# ModuleCarrier-xDot.net
KiCad netlist of a schematic drawn in EAGLE
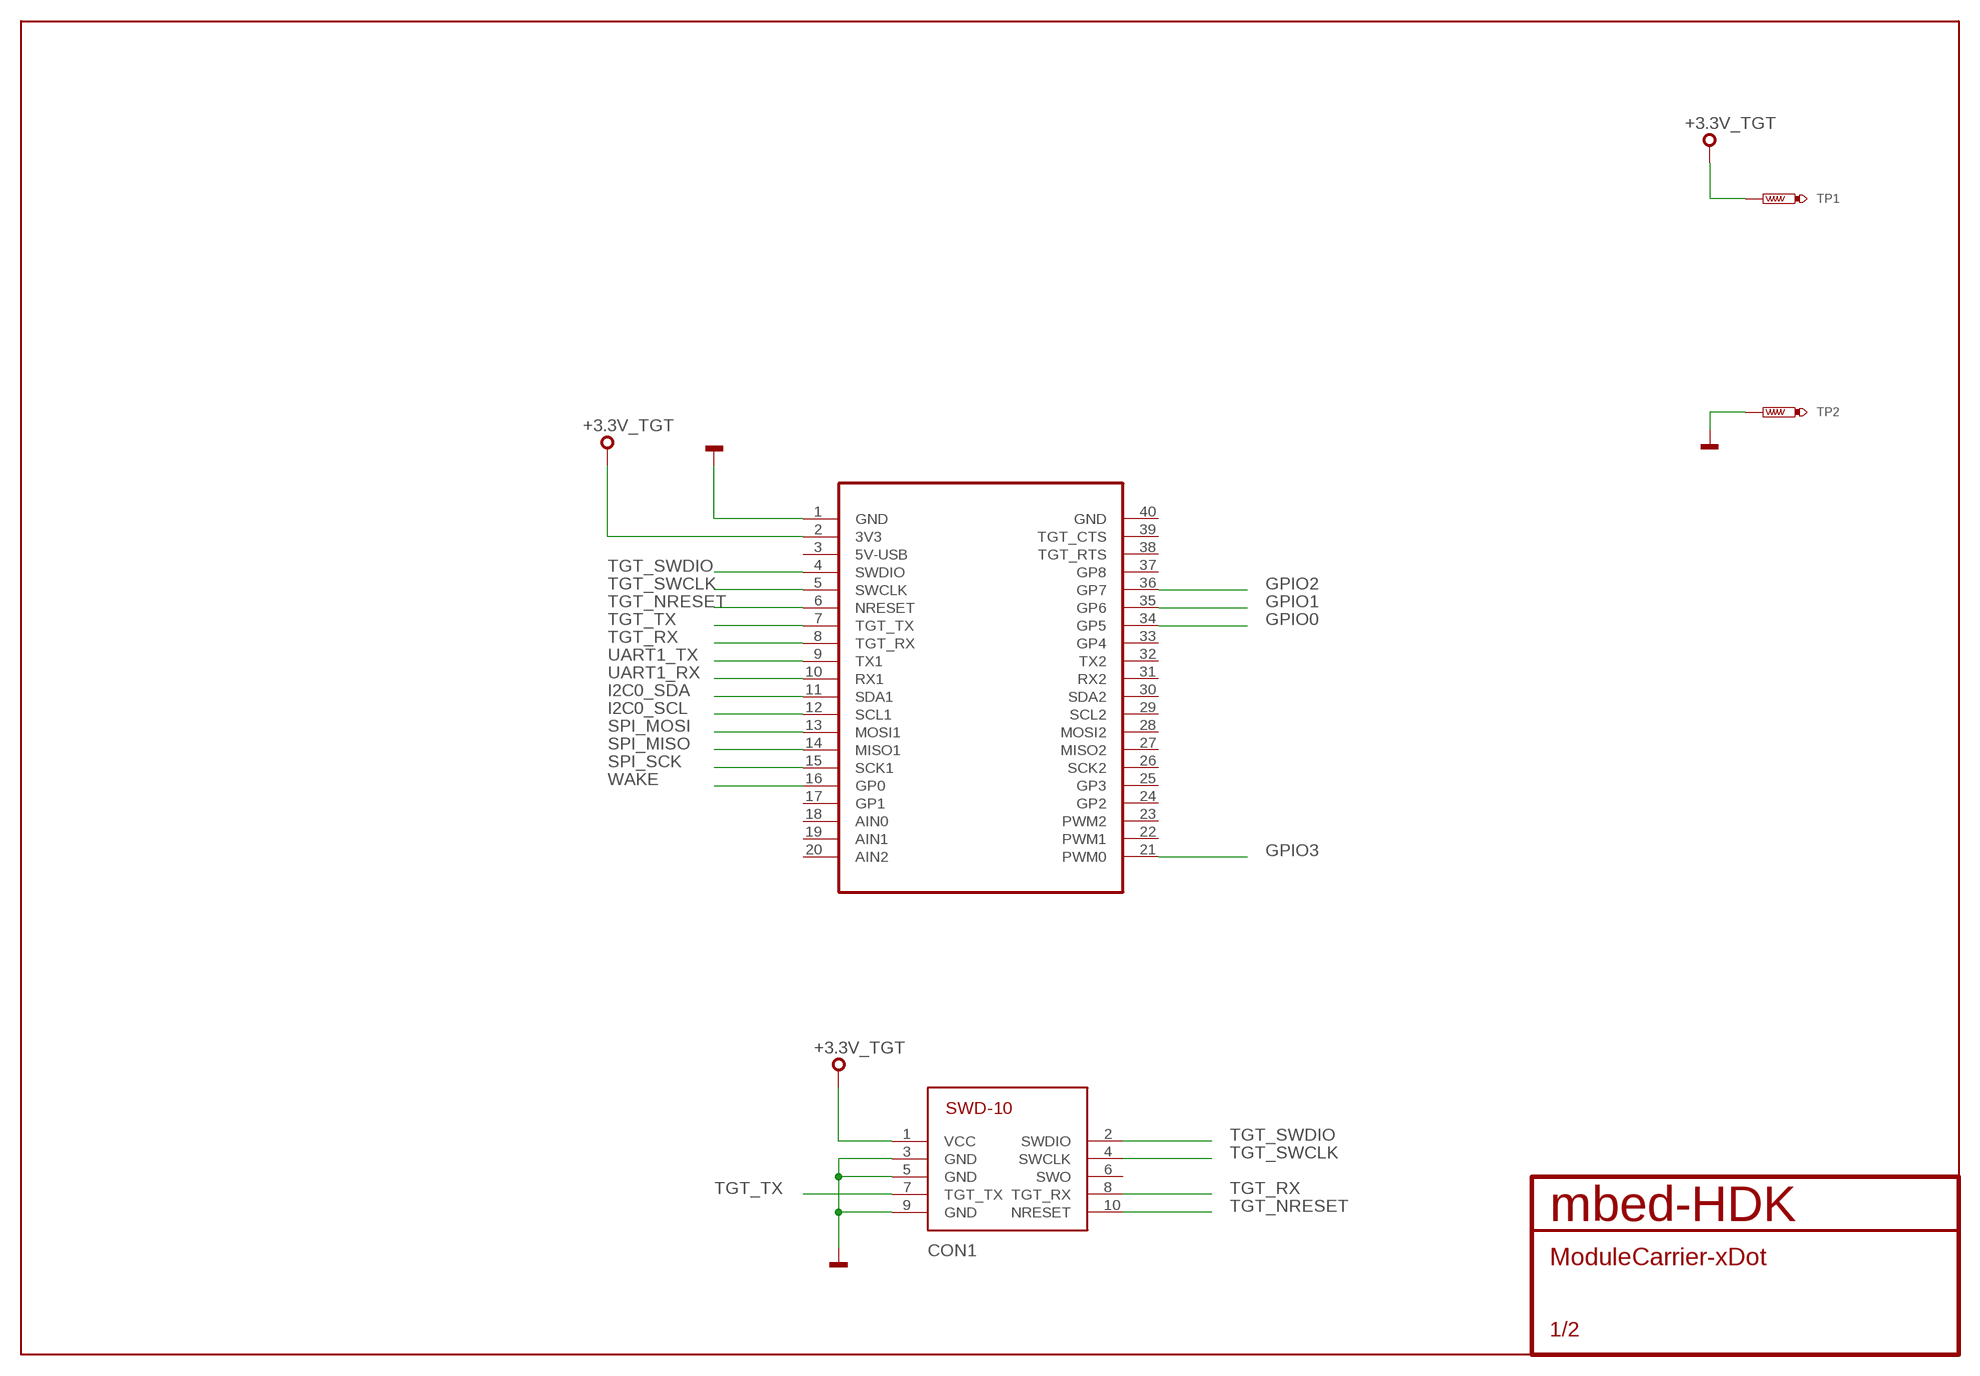
[diagram p0: schematic, sheet 1]
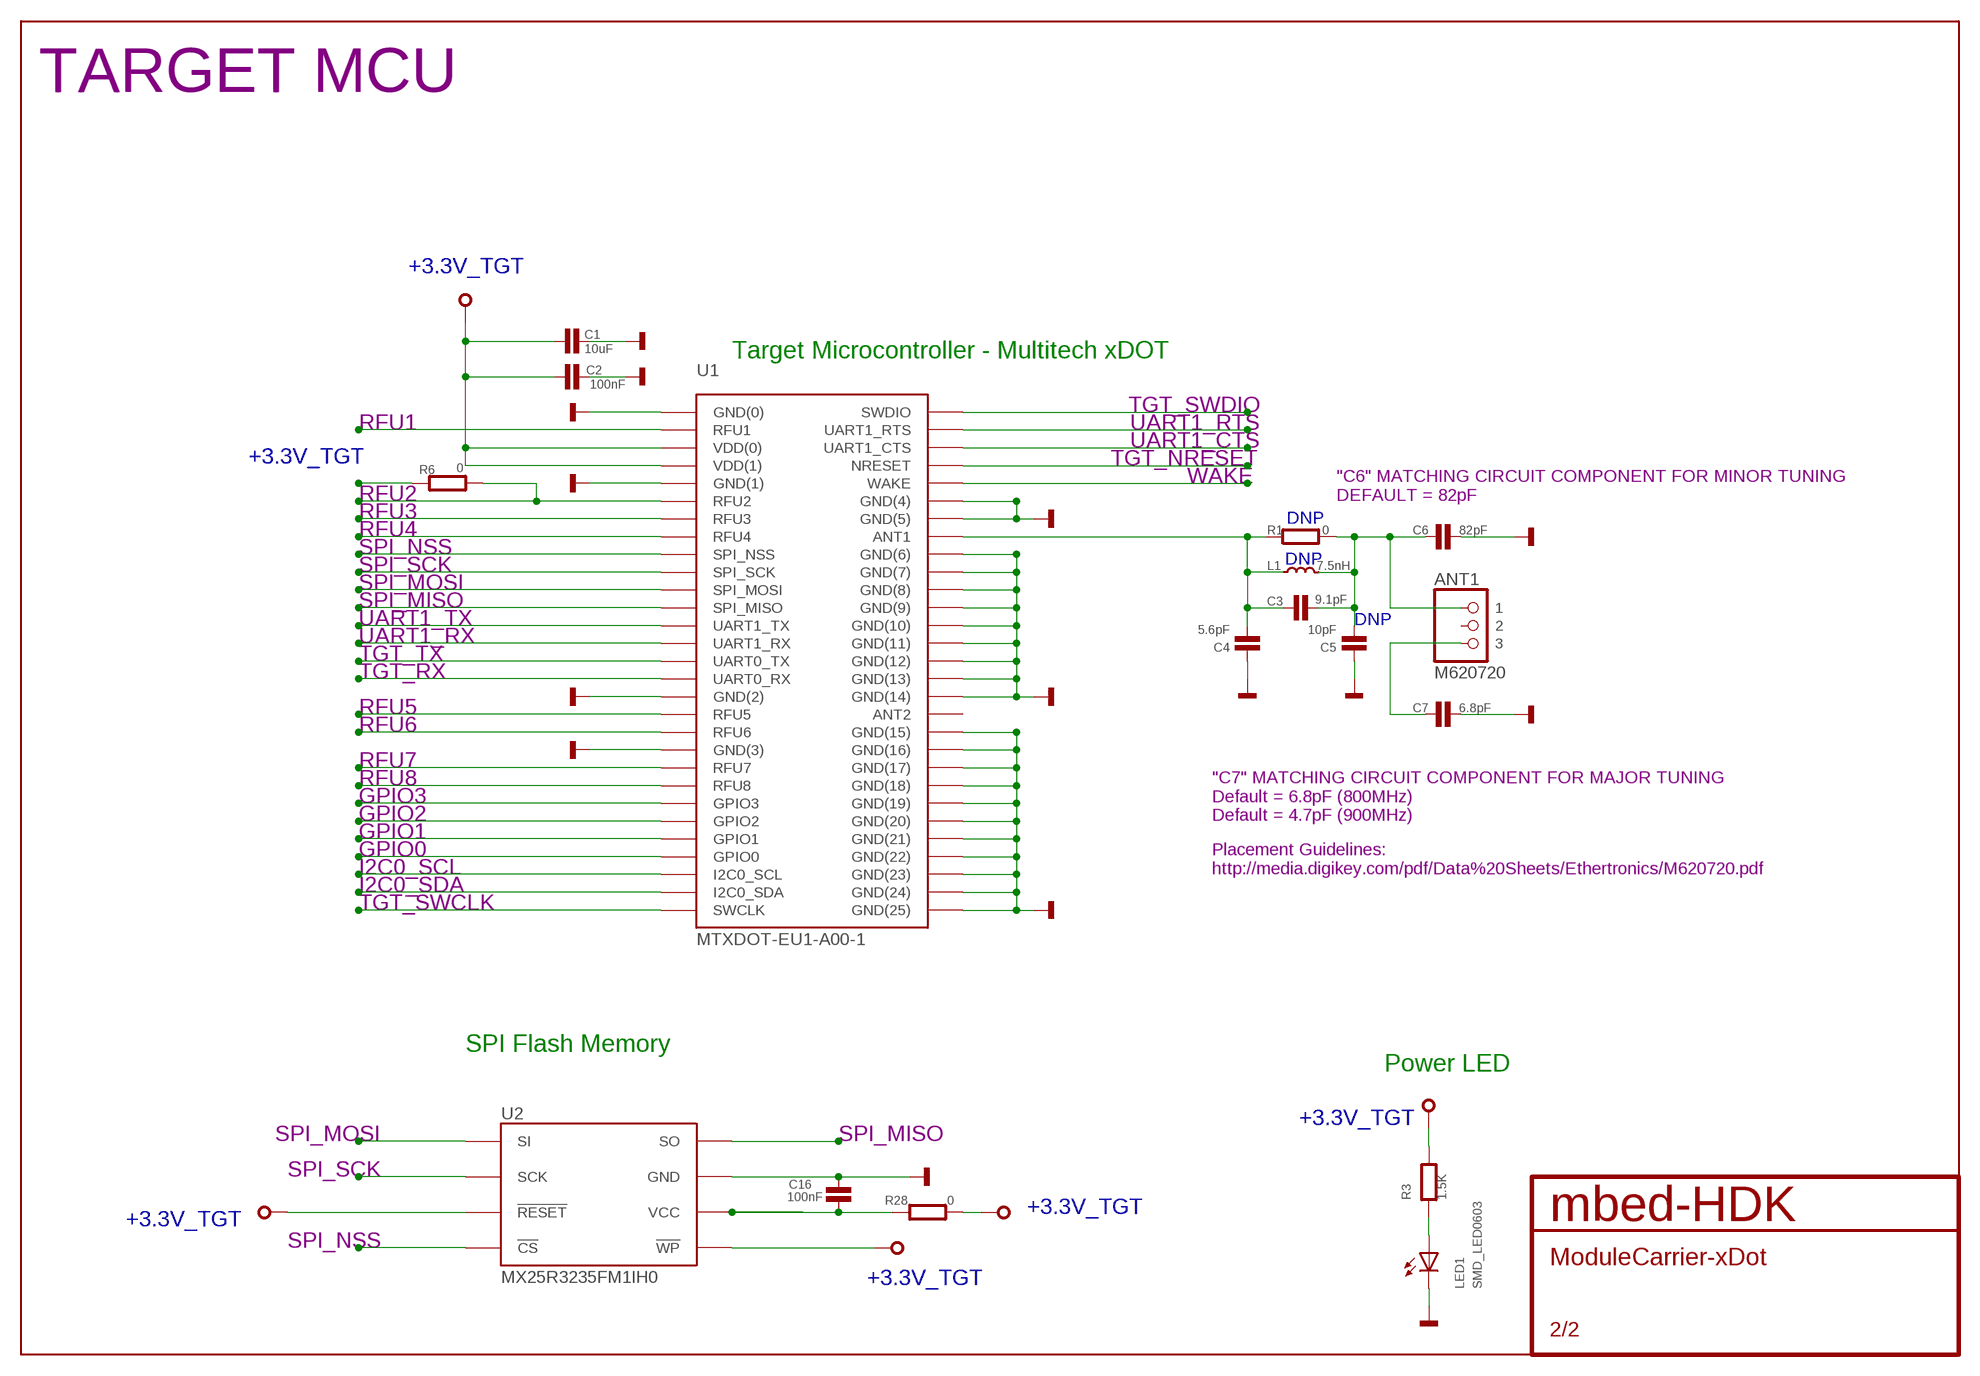
[diagram p1: schematic, sheet 2]

(export (version "E")
  (design (tool "Eeschema 10.0.6"))
  (components
    (comp (ref "CON1")
      (value "SWD-10/TC2050_SMD")
      (footprint "eagle-import:FTSH-105-02")
      (libsource (lib "eagle-import") (part "SWD-10/TC2050_SMD"))
    )
    (comp (ref "TP1")
      (value "TEST-POINT-50R-PTH")
      (footprint "eagle-import:TP50-PTH")
      (libsource (lib "eagle-import") (part "TEST-POINT-50R-PTH"))
    )
    (comp (ref "TP2")
      (value "TEST-POINT-50R-PTH")
      (footprint "eagle-import:TP50-PTH")
      (libsource (lib "eagle-import") (part "TEST-POINT-50R-PTH"))
    )
    (comp (ref "U$1")
      (value "MODULE_DAUGHTER")
      (footprint "eagle-import:MODULE_DAUGHTER")
      (libsource (lib "eagle-import") (part "MODULE_DAUGHTER"))
    )
    (comp (ref "ANT1")
      (value "M620720")
      (footprint "eagle-import:M620720")
      (fields (field (name "MF") "Ethertronics"))
      (libsource (lib "eagle-import") (part "M620720"))
    )
    (comp (ref "C1")
      (value "10uF")
      (footprint "eagle-import:0603")
      (libsource (lib "eagle-import") (part "CAPACITOR0603"))
    )
    (comp (ref "C2")
      (value "100nF")
      (footprint "eagle-import:0603")
      (libsource (lib "eagle-import") (part "CAPACITOR0603"))
    )
    (comp (ref "C3")
      (value "9.1pF")
      (footprint "eagle-import:0402")
      (libsource (lib "eagle-import") (part "CAPACITOR0402"))
    )
    (comp (ref "C4")
      (value "5.6pF")
      (footprint "eagle-import:0402")
      (libsource (lib "eagle-import") (part "CAPACITOR0402"))
    )
    (comp (ref "C5")
      (value "10pF")
      (footprint "eagle-import:0402")
      (libsource (lib "eagle-import") (part "CAPACITOR0402"))
    )
    (comp (ref "C6")
      (value "82pF")
      (footprint "eagle-import:0402")
      (libsource (lib "eagle-import") (part "CAPACITOR0402"))
    )
    (comp (ref "C7")
      (value "6.8pF")
      (footprint "eagle-import:0402")
      (libsource (lib "eagle-import") (part "CAPACITOR0402"))
    )
    (comp (ref "C16")
      (value "100nF")
      (footprint "eagle-import:0603")
      (libsource (lib "eagle-import") (part "CAPACITOR0603"))
    )
    (comp (ref "L1")
      (value "7.5nH")
      (footprint "eagle-import:0402")
      (libsource (lib "eagle-import") (part "INDUCTOR0402"))
    )
    (comp (ref "LED1")
      (value "SMD_LED0603")
      (footprint "eagle-import:CHIPLED_0603")
      (fields (field (name "MF") "Wurth Electronics Inc"))
      (libsource (lib "eagle-import") (part "SMD_LED0603"))
    )
    (comp (ref "R1")
      (value "0")
      (footprint "eagle-import:0402")
      (libsource (lib "eagle-import") (part "RESISTOR0402"))
    )
    (comp (ref "R3")
      (value "1.5K")
      (footprint "eagle-import:0603")
      (libsource (lib "eagle-import") (part "RESISTOR0603"))
    )
    (comp (ref "R6")
      (value "0")
      (footprint "eagle-import:0402")
      (libsource (lib "eagle-import") (part "RESISTOR0402"))
    )
    (comp (ref "R28")
      (value "0")
      (footprint "eagle-import:0603")
      (libsource (lib "eagle-import") (part "RESISTOR0603"))
    )
    (comp (ref "U1")
      (value "MTXDOT-EU1-A00-1")
      (footprint "eagle-import:MTXDOT-EU1_NA1-A00-1")
      (fields (field (name "MF") "Multi-Tech Systems Inc."))
      (libsource (lib "eagle-import") (part "MTXDOT-EU1-A00-1"))
    )
    (comp (ref "U2")
      (value "MX25R3235FM1IH0")
      (footprint "eagle-import:SO8")
      (fields (field (name "MF") "Macronix"))
      (libsource (lib "eagle-import") (part "MX25R3235FM1IH0"))
    )
  )
  (nets
    (net (code "1") (name "+3.3V_TGT") (class "Default")
      (node (ref "C1") (pin "1") (pinfunction "P$1_1") (pintype "passive"))
      (node (ref "C2") (pin "1") (pinfunction "P$1_1") (pintype "passive"))
      (node (ref "CON1") (pin "1") (pinfunction "VCC_1") (pintype "bidirectional"))
      (node (ref "R28") (pin "2") (pinfunction "P$2_2") (pintype "passive"))
      (node (ref "R3") (pin "2") (pinfunction "P$2_2") (pintype "passive"))
      (node (ref "R6") (pin "1") (pinfunction "P$1_1") (pintype "passive"))
      (node (ref "TP1") (pin "TP") (pinfunction "TP_TP") (pintype "input"))
      (node (ref "U$1") (pin "2") (pinfunction "3V3_2") (pintype "bidirectional"))
      (node (ref "U1") (pin "P$3") (pinfunction "VDD(0)_P$3") (pintype "bidirectional"))
      (node (ref "U1") (pin "P$4") (pinfunction "VDD(1)_P$4") (pintype "bidirectional"))
      (node (ref "U2") (pin "3") (pinfunction "~{WP}_3") (pintype "bidirectional"))
      (node (ref "U2") (pin "7") (pinfunction "~{RESET}_7") (pintype "bidirectional"))
    )
    (net (code "2") (name "GND") (class "Default")
      (node (ref "C1") (pin "2") (pinfunction "P$2_2") (pintype "passive"))
      (node (ref "C16") (pin "1") (pinfunction "P$1_1") (pintype "passive"))
      (node (ref "C2") (pin "2") (pinfunction "P$2_2") (pintype "passive"))
      (node (ref "C4") (pin "1") (pinfunction "P$1_1") (pintype "passive"))
      (node (ref "C5") (pin "1") (pinfunction "P$1_1") (pintype "passive"))
      (node (ref "C6") (pin "1") (pinfunction "P$1_1") (pintype "passive"))
      (node (ref "C7") (pin "1") (pinfunction "P$1_1") (pintype "passive"))
      (node (ref "CON1") (pin "3") (pinfunction "GND_3") (pintype "bidirectional"))
      (node (ref "CON1") (pin "5") (pinfunction "GND_5") (pintype "bidirectional"))
      (node (ref "CON1") (pin "9") (pinfunction "GND_9") (pintype "bidirectional"))
      (node (ref "LED1") (pin "C") (pinfunction "C_C") (pintype "passive"))
      (node (ref "TP2") (pin "TP") (pinfunction "TP_TP") (pintype "input"))
      (node (ref "U$1") (pin "1") (pinfunction "GND_1") (pintype "bidirectional"))
      (node (ref "U1") (pin "P$1") (pinfunction "GND(0)_P$1") (pintype "bidirectional"))
      (node (ref "U1") (pin "P$17") (pinfunction "GND(2)_P$17") (pintype "bidirectional"))
      (node (ref "U1") (pin "P$20") (pinfunction "GND(3)_P$20") (pintype "bidirectional"))
      (node (ref "U1") (pin "P$35") (pinfunction "GND(4)_P$35") (pintype "bidirectional"))
      (node (ref "U1") (pin "P$36") (pinfunction "GND(5)_P$36") (pintype "bidirectional"))
      (node (ref "U1") (pin "P$38") (pinfunction "GND(6)_P$38") (pintype "bidirectional"))
      (node (ref "U1") (pin "P$39") (pinfunction "GND(7)_P$39") (pintype "bidirectional"))
      (node (ref "U1") (pin "P$40") (pinfunction "GND(8)_P$40") (pintype "bidirectional"))
      (node (ref "U1") (pin "P$41") (pinfunction "GND(9)_P$41") (pintype "bidirectional"))
      (node (ref "U1") (pin "P$42") (pinfunction "GND(10)_P$42") (pintype "bidirectional"))
      (node (ref "U1") (pin "P$43") (pinfunction "GND(11)_P$43") (pintype "bidirectional"))
      (node (ref "U1") (pin "P$44") (pinfunction "GND(12)_P$44") (pintype "bidirectional"))
      (node (ref "U1") (pin "P$45") (pinfunction "GND(13)_P$45") (pintype "bidirectional"))
      (node (ref "U1") (pin "P$46") (pinfunction "GND(14)_P$46") (pintype "bidirectional"))
      (node (ref "U1") (pin "P$48") (pinfunction "GND(15)_P$48") (pintype "bidirectional"))
      (node (ref "U1") (pin "P$49") (pinfunction "GND(16)_P$49") (pintype "bidirectional"))
      (node (ref "U1") (pin "P$5") (pinfunction "GND(1)_P$5") (pintype "bidirectional"))
      (node (ref "U1") (pin "P$50") (pinfunction "GND(17)_P$50") (pintype "bidirectional"))
      (node (ref "U1") (pin "P$51") (pinfunction "GND(18)_P$51") (pintype "bidirectional"))
      (node (ref "U1") (pin "P$52") (pinfunction "GND(19)_P$52") (pintype "bidirectional"))
      (node (ref "U1") (pin "P$53") (pinfunction "GND(20)_P$53") (pintype "bidirectional"))
      (node (ref "U1") (pin "P$54") (pinfunction "GND(21)_P$54") (pintype "bidirectional"))
      (node (ref "U1") (pin "P$55") (pinfunction "GND(22)_P$55") (pintype "bidirectional"))
      (node (ref "U1") (pin "P$56") (pinfunction "GND(23)_P$56") (pintype "bidirectional"))
      (node (ref "U1") (pin "P$57") (pinfunction "GND(24)_P$57") (pintype "bidirectional"))
      (node (ref "U1") (pin "P$58") (pinfunction "GND(25)_P$58") (pintype "bidirectional"))
      (node (ref "U2") (pin "4") (pinfunction "GND_4") (pintype "bidirectional"))
    )
    (net (code "3") (name "GPIO0") (class "Default")
      (node (ref "U$1") (pin "34") (pinfunction "GP5_34") (pintype "bidirectional"))
      (node (ref "U1") (pin "P$26") (pinfunction "GPIO0_P$26") (pintype "bidirectional"))
    )
    (net (code "4") (name "GPIO1") (class "Default")
      (node (ref "U$1") (pin "35") (pinfunction "GP6_35") (pintype "bidirectional"))
      (node (ref "U1") (pin "P$25") (pinfunction "GPIO1_P$25") (pintype "bidirectional"))
    )
    (net (code "5") (name "GPIO2") (class "Default")
      (node (ref "U$1") (pin "36") (pinfunction "GP7_36") (pintype "bidirectional"))
      (node (ref "U1") (pin "P$24") (pinfunction "GPIO2_P$24") (pintype "bidirectional"))
    )
    (net (code "6") (name "GPIO3") (class "Default")
      (node (ref "U$1") (pin "21") (pinfunction "PWM0_21") (pintype "bidirectional"))
      (node (ref "U1") (pin "P$23") (pinfunction "GPIO3_P$23") (pintype "bidirectional"))
    )
    (net (code "7") (name "I2C0_SCL") (class "Default")
      (node (ref "U$1") (pin "12") (pinfunction "SCL1_12") (pintype "bidirectional"))
      (node (ref "U1") (pin "P$27") (pinfunction "I2C0_SCL_P$27") (pintype "bidirectional"))
    )
    (net (code "8") (name "I2C0_SDA") (class "Default")
      (node (ref "U$1") (pin "11") (pinfunction "SDA1_11") (pintype "bidirectional"))
      (node (ref "U1") (pin "P$28") (pinfunction "I2C0_SDA_P$28") (pintype "bidirectional"))
    )
    (net (code "9") (name "Net-(ANT1-1)") (class "Default")
      (node (ref "ANT1") (pin "P$1") (pinfunction "1_P$1") (pintype "passive"))
      (node (ref "C3") (pin "2") (pinfunction "P$2_2") (pintype "passive"))
      (node (ref "C5") (pin "2") (pinfunction "P$2_2") (pintype "passive"))
      (node (ref "C6") (pin "2") (pinfunction "P$2_2") (pintype "passive"))
      (node (ref "L1") (pin "2") (pinfunction "P$2_2") (pintype "bidirectional"))
      (node (ref "R1") (pin "2") (pinfunction "P$2_2") (pintype "passive"))
    )
    (net (code "10") (name "Net-(ANT1-3)") (class "Default")
      (node (ref "ANT1") (pin "P$3") (pinfunction "3_P$3") (pintype "passive"))
      (node (ref "C7") (pin "2") (pinfunction "P$2_2") (pintype "passive"))
    )
    (net (code "11") (name "Net-(C3-P$1)") (class "Default")
      (node (ref "C3") (pin "1") (pinfunction "P$1_1") (pintype "passive"))
      (node (ref "C4") (pin "2") (pinfunction "P$2_2") (pintype "passive"))
      (node (ref "L1") (pin "1") (pinfunction "P$1_1") (pintype "bidirectional"))
      (node (ref "R1") (pin "1") (pinfunction "P$1_1") (pintype "passive"))
      (node (ref "U1") (pin "P$37") (pinfunction "ANT1_P$37") (pintype "bidirectional"))
    )
    (net (code "12") (name "Net-(C16-P$2)") (class "Default")
      (node (ref "C16") (pin "2") (pinfunction "P$2_2") (pintype "passive"))
      (node (ref "R28") (pin "1") (pinfunction "P$1_1") (pintype "passive"))
      (node (ref "U2") (pin "8") (pinfunction "VCC_8") (pintype "bidirectional"))
    )
    (net (code "13") (name "Net-(R3-P$1)") (class "Default")
      (node (ref "LED1") (pin "A") (pinfunction "A_A") (pintype "passive"))
      (node (ref "R3") (pin "1") (pinfunction "P$1_1") (pintype "passive"))
    )
    (net (code "14") (name "RFU1") (class "Default")
      (node (ref "U1") (pin "P$2") (pinfunction "RFU1_P$2") (pintype "bidirectional"))
    )
    (net (code "15") (name "RFU2") (class "Default")
      (node (ref "R6") (pin "2") (pinfunction "P$2_2") (pintype "passive"))
      (node (ref "U1") (pin "P$6") (pinfunction "RFU2_P$6") (pintype "bidirectional"))
    )
    (net (code "16") (name "RFU3") (class "Default")
      (node (ref "U1") (pin "P$7") (pinfunction "RFU3_P$7") (pintype "bidirectional"))
    )
    (net (code "17") (name "RFU4") (class "Default")
      (node (ref "U1") (pin "P$8") (pinfunction "RFU4_P$8") (pintype "bidirectional"))
    )
    (net (code "18") (name "RFU5") (class "Default")
      (node (ref "U1") (pin "P$18") (pinfunction "RFU5_P$18") (pintype "bidirectional"))
    )
    (net (code "19") (name "RFU6") (class "Default")
      (node (ref "U1") (pin "P$19") (pinfunction "RFU6_P$19") (pintype "bidirectional"))
    )
    (net (code "20") (name "RFU7") (class "Default")
      (node (ref "U1") (pin "P$21") (pinfunction "RFU7_P$21") (pintype "bidirectional"))
    )
    (net (code "21") (name "RFU8") (class "Default")
      (node (ref "U1") (pin "P$22") (pinfunction "RFU8_P$22") (pintype "bidirectional"))
    )
    (net (code "22") (name "SPI_MISO") (class "Default")
      (node (ref "U$1") (pin "14") (pinfunction "MISO1_14") (pintype "bidirectional"))
      (node (ref "U1") (pin "P$12") (pinfunction "SPI_MISO_P$12") (pintype "bidirectional"))
      (node (ref "U2") (pin "2") (pinfunction "SO_2") (pintype "bidirectional"))
    )
    (net (code "23") (name "SPI_MOSI") (class "Default")
      (node (ref "U$1") (pin "13") (pinfunction "MOSI1_13") (pintype "bidirectional"))
      (node (ref "U1") (pin "P$11") (pinfunction "SPI_MOSI_P$11") (pintype "bidirectional"))
      (node (ref "U2") (pin "5") (pinfunction "SI_5") (pintype "bidirectional"))
    )
    (net (code "24") (name "SPI_NSS") (class "Default")
      (node (ref "U1") (pin "P$9") (pinfunction "SPI_NSS_P$9") (pintype "bidirectional"))
      (node (ref "U2") (pin "1") (pinfunction "~{CS}_1") (pintype "bidirectional"))
    )
    (net (code "25") (name "SPI_SCK") (class "Default")
      (node (ref "U$1") (pin "15") (pinfunction "SCK1_15") (pintype "bidirectional"))
      (node (ref "U1") (pin "P$10") (pinfunction "SPI_SCK_P$10") (pintype "bidirectional"))
      (node (ref "U2") (pin "6") (pinfunction "SCK_6") (pintype "bidirectional"))
    )
    (net (code "26") (name "TGT_NRESET") (class "Default")
      (node (ref "CON1") (pin "10") (pinfunction "NRESET_10") (pintype "bidirectional"))
      (node (ref "U$1") (pin "6") (pinfunction "NRESET_6") (pintype "bidirectional"))
      (node (ref "U1") (pin "P$33") (pinfunction "NRESET_P$33") (pintype "bidirectional"))
    )
    (net (code "27") (name "TGT_RX") (class "Default")
      (node (ref "CON1") (pin "8") (pinfunction "TGT_RX_8") (pintype "bidirectional"))
      (node (ref "U$1") (pin "8") (pinfunction "TGT_RX_8") (pintype "bidirectional"))
      (node (ref "U1") (pin "P$16") (pinfunction "UART0_RX_P$16") (pintype "bidirectional"))
    )
    (net (code "28") (name "TGT_SWCLK") (class "Default")
      (node (ref "CON1") (pin "4") (pinfunction "SWCLK_4") (pintype "bidirectional"))
      (node (ref "U$1") (pin "5") (pinfunction "SWCLK_5") (pintype "bidirectional"))
      (node (ref "U1") (pin "P$29") (pinfunction "SWCLK_P$29") (pintype "bidirectional"))
    )
    (net (code "29") (name "TGT_SWDIO") (class "Default")
      (node (ref "CON1") (pin "2") (pinfunction "SWDIO_2") (pintype "bidirectional"))
      (node (ref "U$1") (pin "4") (pinfunction "SWDIO_4") (pintype "bidirectional"))
      (node (ref "U1") (pin "P$30") (pinfunction "SWDIO_P$30") (pintype "bidirectional"))
    )
    (net (code "30") (name "TGT_TX") (class "Default")
      (node (ref "CON1") (pin "7") (pinfunction "TGT_TX_7") (pintype "bidirectional"))
      (node (ref "U$1") (pin "7") (pinfunction "TGT_TX_7") (pintype "bidirectional"))
      (node (ref "U1") (pin "P$15") (pinfunction "UART0_TX_P$15") (pintype "bidirectional"))
    )
    (net (code "31") (name "UART1_CTS") (class "Default")
      (node (ref "U1") (pin "P$32") (pinfunction "UART1_CTS_P$32") (pintype "bidirectional"))
    )
    (net (code "32") (name "UART1_RTS") (class "Default")
      (node (ref "U1") (pin "P$31") (pinfunction "UART1_RTS_P$31") (pintype "bidirectional"))
    )
    (net (code "33") (name "UART1_RX") (class "Default")
      (node (ref "U$1") (pin "10") (pinfunction "RX1_10") (pintype "bidirectional"))
      (node (ref "U1") (pin "P$14") (pinfunction "UART1_RX_P$14") (pintype "bidirectional"))
    )
    (net (code "34") (name "UART1_TX") (class "Default")
      (node (ref "U$1") (pin "9") (pinfunction "TX1_9") (pintype "bidirectional"))
      (node (ref "U1") (pin "P$13") (pinfunction "UART1_TX_P$13") (pintype "bidirectional"))
    )
    (net (code "35") (name "WAKE") (class "Default")
      (node (ref "U$1") (pin "16") (pinfunction "GP0_16") (pintype "bidirectional"))
      (node (ref "U1") (pin "P$34") (pinfunction "WAKE_P$34") (pintype "bidirectional"))
    )
    (net (code "36") (name "unconnected-(ANT1-2-PadP$2)") (class "Default")
      (node (ref "ANT1") (pin "P$2") (pinfunction "2_P$2") (pintype "passive"))
    )
    (net (code "37") (name "unconnected-(CON1-SWO-Pad6)") (class "Default")
      (node (ref "CON1") (pin "6") (pinfunction "SWO_6") (pintype "bidirectional"))
    )
    (net (code "38") (name "unconnected-(U$1-5V-USB-Pad3)") (class "Default")
      (node (ref "U$1") (pin "3") (pinfunction "5V-USB_3") (pintype "bidirectional"))
    )
    (net (code "39") (name "unconnected-(U$1-AIN0-Pad18)") (class "Default")
      (node (ref "U$1") (pin "18") (pinfunction "AIN0_18") (pintype "bidirectional"))
    )
    (net (code "40") (name "unconnected-(U$1-AIN1-Pad19)") (class "Default")
      (node (ref "U$1") (pin "19") (pinfunction "AIN1_19") (pintype "bidirectional"))
    )
    (net (code "41") (name "unconnected-(U$1-AIN2-Pad20)") (class "Default")
      (node (ref "U$1") (pin "20") (pinfunction "AIN2_20") (pintype "bidirectional"))
    )
    (net (code "42") (name "unconnected-(U$1-GND-Pad40)") (class "Default")
      (node (ref "U$1") (pin "40") (pinfunction "GND_40") (pintype "bidirectional"))
    )
    (net (code "43") (name "unconnected-(U$1-GP1-Pad17)") (class "Default")
      (node (ref "U$1") (pin "17") (pinfunction "GP1_17") (pintype "bidirectional"))
    )
    (net (code "44") (name "unconnected-(U$1-GP2-Pad24)") (class "Default")
      (node (ref "U$1") (pin "24") (pinfunction "GP2_24") (pintype "bidirectional"))
    )
    (net (code "45") (name "unconnected-(U$1-GP3-Pad25)") (class "Default")
      (node (ref "U$1") (pin "25") (pinfunction "GP3_25") (pintype "bidirectional"))
    )
    (net (code "46") (name "unconnected-(U$1-GP4-Pad33)") (class "Default")
      (node (ref "U$1") (pin "33") (pinfunction "GP4_33") (pintype "bidirectional"))
    )
    (net (code "47") (name "unconnected-(U$1-GP8-Pad37)") (class "Default")
      (node (ref "U$1") (pin "37") (pinfunction "GP8_37") (pintype "bidirectional"))
    )
    (net (code "48") (name "unconnected-(U$1-MISO2-Pad27)") (class "Default")
      (node (ref "U$1") (pin "27") (pinfunction "MISO2_27") (pintype "bidirectional"))
    )
    (net (code "49") (name "unconnected-(U$1-MOSI2-Pad28)") (class "Default")
      (node (ref "U$1") (pin "28") (pinfunction "MOSI2_28") (pintype "bidirectional"))
    )
    (net (code "50") (name "unconnected-(U$1-PWM1-Pad22)") (class "Default")
      (node (ref "U$1") (pin "22") (pinfunction "PWM1_22") (pintype "bidirectional"))
    )
    (net (code "51") (name "unconnected-(U$1-PWM2-Pad23)") (class "Default")
      (node (ref "U$1") (pin "23") (pinfunction "PWM2_23") (pintype "bidirectional"))
    )
    (net (code "52") (name "unconnected-(U$1-RX2-Pad31)") (class "Default")
      (node (ref "U$1") (pin "31") (pinfunction "RX2_31") (pintype "bidirectional"))
    )
    (net (code "53") (name "unconnected-(U$1-SCK2-Pad26)") (class "Default")
      (node (ref "U$1") (pin "26") (pinfunction "SCK2_26") (pintype "bidirectional"))
    )
    (net (code "54") (name "unconnected-(U$1-SCL2-Pad29)") (class "Default")
      (node (ref "U$1") (pin "29") (pinfunction "SCL2_29") (pintype "bidirectional"))
    )
    (net (code "55") (name "unconnected-(U$1-SDA2-Pad30)") (class "Default")
      (node (ref "U$1") (pin "30") (pinfunction "SDA2_30") (pintype "bidirectional"))
    )
    (net (code "56") (name "unconnected-(U$1-TGT_CTS-Pad39)") (class "Default")
      (node (ref "U$1") (pin "39") (pinfunction "TGT_CTS_39") (pintype "bidirectional"))
    )
    (net (code "57") (name "unconnected-(U$1-TGT_RTS-Pad38)") (class "Default")
      (node (ref "U$1") (pin "38") (pinfunction "TGT_RTS_38") (pintype "bidirectional"))
    )
    (net (code "58") (name "unconnected-(U$1-TX2-Pad32)") (class "Default")
      (node (ref "U$1") (pin "32") (pinfunction "TX2_32") (pintype "bidirectional"))
    )
    (net (code "59") (name "unconnected-(U1-ANT2-PadP$47)") (class "Default")
      (node (ref "U1") (pin "P$47") (pinfunction "ANT2_P$47") (pintype "bidirectional"))
    )
  )
)
